# LMH2121.net
KiCad netlist of a schematic drawn in Altium Designer
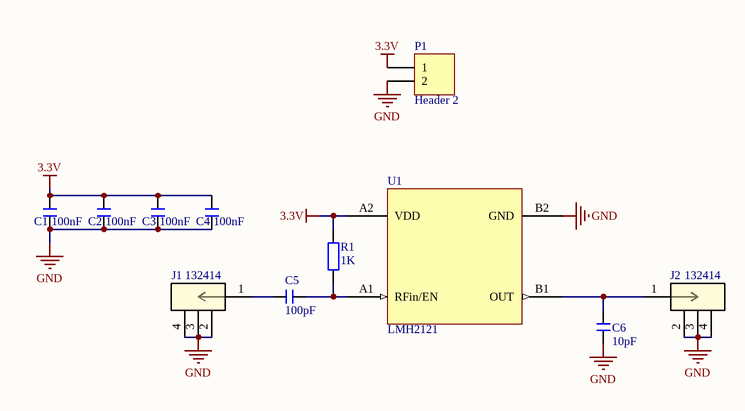
[diagram p0: LMH2121.SchDoc]

(export (version "E")
  (design (tool "Eeschema 10.0.6"))
  (components
    (comp (ref "C1")
      (value "100nF")
      (footprint "C 0402_L")
      (description "贴片电容")
      (libsource (lib "01 - 电容-电阻-电感") (part "C"))
    )
    (comp (ref "C2")
      (value "100nF")
      (footprint "C 0402_L")
      (description "贴片电容")
      (libsource (lib "01 - 电容-电阻-电感") (part "C"))
    )
    (comp (ref "C3")
      (value "100nF")
      (footprint "C 0402_L")
      (description "贴片电容")
      (libsource (lib "01 - 电容-电阻-电感") (part "C"))
    )
    (comp (ref "C4")
      (value "100nF")
      (footprint "C 0402_L")
      (description "贴片电容")
      (libsource (lib "01 - 电容-电阻-电感") (part "C"))
    )
    (comp (ref "C5")
      (value "100pF")
      (footprint "C 0402_L")
      (description "贴片电容")
      (libsource (lib "01 - 电容-电阻-电感") (part "C"))
    )
    (comp (ref "C6")
      (value "10pF")
      (footprint "C 0402_L")
      (description "贴片电容")
      (libsource (lib "01 - 电容-电阻-电感") (part "C"))
    )
    (comp (ref "J1")
      (value "132414")
      (footprint "CONN_132414_AMP")
      (description "No Description Available")
      (fields (field (name "COPYRIGHT") "Copyright (C) 2022 Ultra Librarian. All rights reserved."))
      (libsource (lib "") (part "132414_1"))
    )
    (comp (ref "J2")
      (value "132414")
      (footprint "CONN_132414_AMP")
      (description "No Description Available")
      (fields (field (name "COPYRIGHT") "Copyright (C) 2022 Ultra Librarian. All rights reserved."))
      (libsource (lib "细针大偏脚SMA(用这个)") (part "132414"))
    )
    (comp (ref "P1")
      (value "Header 2")
      (footprint "HDR1X2")
      (description "Header, 2-Pin")
      (fields (field (name "PUBLISHER") "Altium Limited"))
      (libsource (lib "Miscellaneous Connectors") (part "Header 2"))
    )
    (comp (ref "R1")
      (value "1K")
      (footprint "R 0402_L")
      (description "贴片电阻")
      (libsource (lib "01 - 电容-电阻-电感") (part "R"))
    )
    (comp (ref "U1")
      (value "LMH2121")
      (footprint "BGA4N50P2X2_88X88X50N")
      (description "3 GHz Fast-Responding Linear Power Detector with 40 dB Dynamic Range")
      (libsource (lib "LMH2121") (part "LMH2121"))
    )
  )
  (nets
    (net (code "1") (name "3.3V") (class "Default")
      (node (ref "C1") (pin "2") (pinfunction "2_2") (pintype "passive"))
      (node (ref "C2") (pin "2") (pinfunction "2_2") (pintype "passive"))
      (node (ref "C3") (pin "2") (pinfunction "2_2") (pintype "passive"))
      (node (ref "C4") (pin "2") (pinfunction "2_2") (pintype "passive"))
      (node (ref "P1") (pin "1") (pinfunction "1_1") (pintype "passive"))
      (node (ref "R1") (pin "2") (pinfunction "2_2") (pintype "passive"))
      (node (ref "U1") (pin "A2") (pinfunction "VDD_A2") (pintype "power_in"))
    )
    (net (code "2") (name "GND") (class "Default")
      (node (ref "C1") (pin "1") (pinfunction "1_1") (pintype "passive"))
      (node (ref "C2") (pin "1") (pinfunction "1_1") (pintype "passive"))
      (node (ref "C3") (pin "1") (pinfunction "1_1") (pintype "passive"))
      (node (ref "C4") (pin "1") (pinfunction "1_1") (pintype "passive"))
      (node (ref "C6") (pin "1") (pinfunction "1_1") (pintype "passive"))
      (node (ref "J1") (pin "2") (pinfunction "2_2") (pintype "passive"))
      (node (ref "J1") (pin "3") (pinfunction "3_3") (pintype "passive"))
      (node (ref "J1") (pin "4") (pinfunction "4_4") (pintype "passive"))
      (node (ref "J2") (pin "2") (pinfunction "2_2") (pintype "passive"))
      (node (ref "J2") (pin "3") (pinfunction "3_3") (pintype "passive"))
      (node (ref "J2") (pin "4") (pinfunction "4_4") (pintype "passive"))
      (node (ref "P1") (pin "2") (pinfunction "2_2") (pintype "passive"))
      (node (ref "U1") (pin "B2") (pinfunction "GND_B2") (pintype "power_in"))
    )
    (net (code "3") (name "Net-(C5-Pad1)") (class "Default")
      (node (ref "C5") (pin "1") (pinfunction "1_1") (pintype "passive"))
      (node (ref "J1") (pin "1") (pinfunction "1_1") (pintype "passive"))
    )
    (net (code "4") (name "Net-(U1-OUT)") (class "Default")
      (node (ref "C6") (pin "2") (pinfunction "2_2") (pintype "passive"))
      (node (ref "J2") (pin "1") (pinfunction "1_1") (pintype "passive"))
      (node (ref "U1") (pin "B1") (pinfunction "OUT_B1") (pintype "output"))
    )
    (net (code "5") (name "Net-(U1-RFin{slash}EN)") (class "Default")
      (node (ref "C5") (pin "2") (pinfunction "2_2") (pintype "passive"))
      (node (ref "R1") (pin "1") (pinfunction "1_1") (pintype "passive"))
      (node (ref "U1") (pin "A1") (pinfunction "RFin/EN_A1") (pintype "input"))
    )
  )
)
